# esp_all.net
KiCad netlist of a schematic drawn in EAGLE
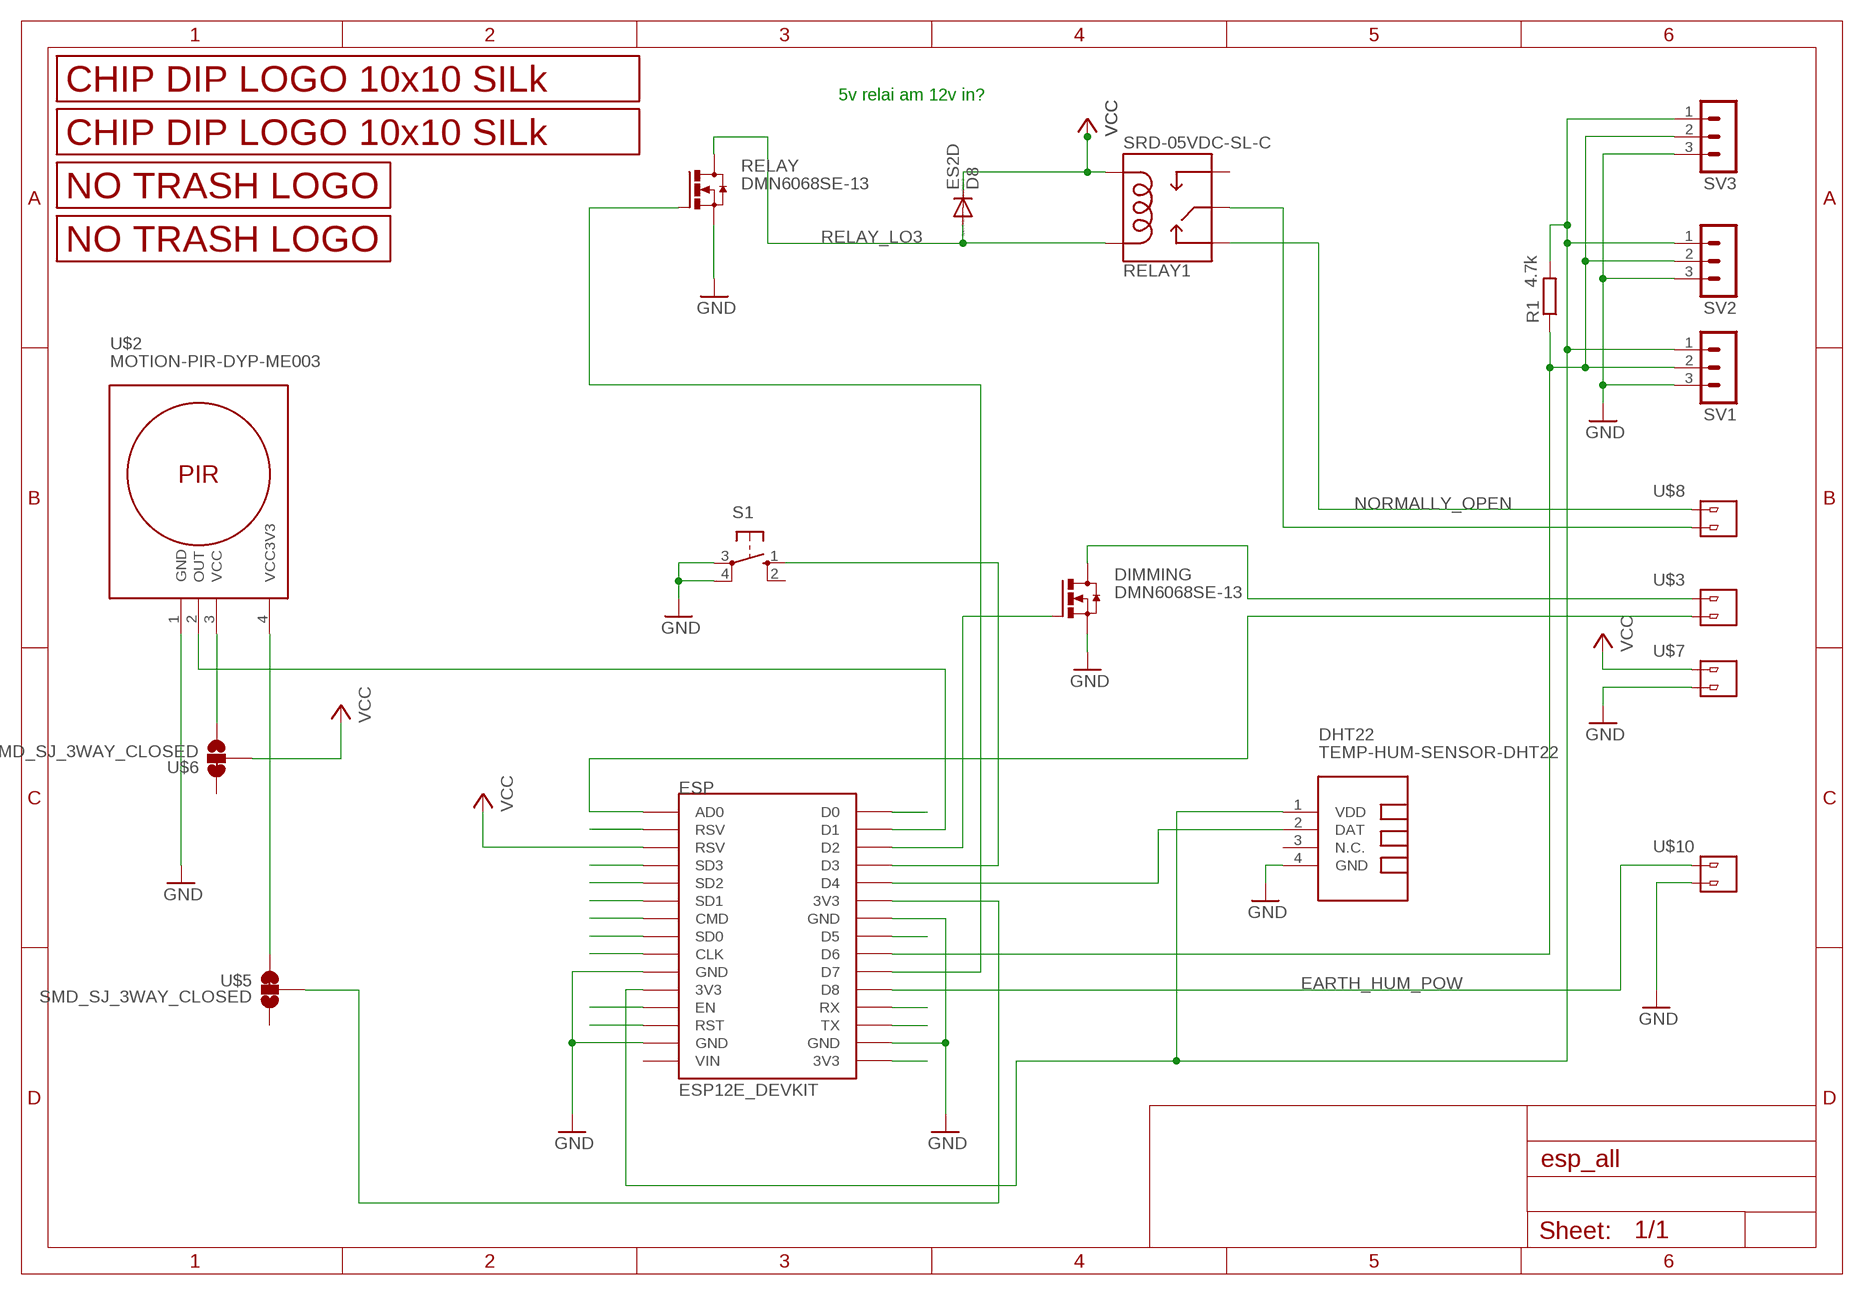
[diagram p0: schematic, sheet 1]

(export (version "E")
  (design (tool "Eeschema 10.0.6"))
  (components
    (comp (ref "D8")
      (value "ES2D")
      (footprint "eagle-import:SMB")
      (libsource (lib "eagle-import") (part "DIODE-SMB"))
    )
    (comp (ref "DHT22")
      (value "TEMP-HUM-SENSOR-DHT22")
      (footprint "eagle-import:TEMP-HUM-SENSOR-DHT22")
      (libsource (lib "eagle-import") (part "TEMP-HUM-SENSOR-DHT22"))
    )
    (comp (ref "DIMMING")
      (value "DMN6068SE-13")
      (footprint "eagle-import:SOT223")
      (libsource (lib "eagle-import") (part "NMOSFET_SMD_223"))
    )
    (comp (ref "ESP")
      (value "ESP12E_DEVKIT")
      (footprint "eagle-import:ESP12E_DEVKIT")
      (libsource (lib "eagle-import") (part "ESP12E_DEVKIT"))
    )
    (comp (ref "R1")
      (value "4.7k")
      (footprint "eagle-import:M0805")
      (libsource (lib "eagle-import") (part "R-EU_M0805"))
    )
    (comp (ref "RELAY")
      (value "DMN6068SE-13")
      (footprint "eagle-import:SOT223")
      (libsource (lib "eagle-import") (part "NMOSFET_SMD_223"))
    )
    (comp (ref "RELAY1")
      (value "SRD-05VDC-SL-C")
      (footprint "eagle-import:SRD-05VDC-SL-C")
      (libsource (lib "eagle-import") (part "RELAYPTH"))
    )
    (comp (ref "S1")
      (value "40/XX")
      (footprint "eagle-import:B3F_40XX")
      (libsource (lib "eagle-import") (part "40/XX"))
    )
    (comp (ref "SV1")
      (value "MA03-1")
      (footprint "eagle-import:MA03-1")
      (libsource (lib "eagle-import") (part "MA03-1"))
    )
    (comp (ref "SV2")
      (value "MA03-1")
      (footprint "eagle-import:MA03-1")
      (libsource (lib "eagle-import") (part "MA03-1"))
    )
    (comp (ref "SV3")
      (value "MA03-1")
      (footprint "eagle-import:MA03-1")
      (libsource (lib "eagle-import") (part "MA03-1"))
    )
    (comp (ref "U$1")
      (value "LOGO_10X10_SILK")
      (footprint "eagle-import:LOGO2_10X10_SILK")
      (libsource (lib "eagle-import") (part "LOGO_10X10_SILK"))
    )
    (comp (ref "U$2")
      (value "MOTION-PIR-DYP-ME003")
      (footprint "eagle-import:MOTION-PIR-DYP-ME003")
      (libsource (lib "eagle-import") (part "MOTION-PIR-DYP-ME003"))
    )
    (comp (ref "U$3")
      (value "V1")
      (footprint "eagle-import:2_SCREW_PIN")
      (libsource (lib "eagle-import") (part "2_PIN_CONNECTOR"))
    )
    (comp (ref "U$4")
      (value "LOGO_NO_TRASHNO_TRASH")
      (footprint "eagle-import:LOGO_ROHS_NO_TRASH")
      (libsource (lib "eagle-import") (part "LOGO_NO_TRASHNO_TRASH"))
    )
    (comp (ref "U$5")
      (value "SMD_SJ_3WAY_CLOSED")
      (footprint "eagle-import:SMD_SJ_3WAY_CLOSED")
      (libsource (lib "eagle-import") (part "SMD_SJ_3WAY_CLOSED"))
    )
    (comp (ref "U$6")
      (value "SMD_SJ_3WAY_CLOSED")
      (footprint "eagle-import:SMD_SJ_3WAY_CLOSED")
      (libsource (lib "eagle-import") (part "SMD_SJ_3WAY_CLOSED"))
    )
    (comp (ref "U$7")
      (value "V1")
      (footprint "eagle-import:2_SCREW_PIN")
      (libsource (lib "eagle-import") (part "2_PIN_CONNECTOR"))
    )
    (comp (ref "U$8")
      (value "V1")
      (footprint "eagle-import:2_SCREW_PIN")
      (libsource (lib "eagle-import") (part "2_PIN_CONNECTOR"))
    )
    (comp (ref "U$9")
      (value "LOGO_NO_TRASHROHS")
      (footprint "eagle-import:LOGO_ROHS_SYM")
      (libsource (lib "eagle-import") (part "LOGO_NO_TRASHROHS"))
    )
    (comp (ref "U$10")
      (value "V1")
      (footprint "eagle-import:2_SCREW_PIN")
      (libsource (lib "eagle-import") (part "2_PIN_CONNECTOR"))
    )
    (comp (ref "U$11")
      (value "LOGO_10X10_SILK")
      (footprint "eagle-import:LOGO2_10X10_SILK")
      (libsource (lib "eagle-import") (part "LOGO_10X10_SILK"))
    )
  )
  (nets
    (net (code "1") (name "/EARTH_HUM_POW") (class "Default")
      (node (ref "ESP") (pin "D8") (pinfunction "D8_D8") (pintype "bidirectional"))
      (node (ref "U$10") (pin "P$1") (pinfunction "1_P$1") (pintype "passive"))
    )
    (net (code "2") (name "/NORMALLY_OPEN") (class "Default")
      (node (ref "RELAY1") (pin "SWCLOSED") (pinfunction "SWCLOSE_SWCLOSED") (pintype "bidirectional"))
      (node (ref "U$8") (pin "P$1") (pinfunction "1_P$1") (pintype "passive"))
    )
    (net (code "3") (name "/RELAY_LO3") (class "Default")
      (node (ref "D8") (pin "A") (pinfunction "A_A") (pintype "passive"))
      (node (ref "RELAY") (pin "2") (pinfunction "D_2") (pintype "passive"))
      (node (ref "RELAY") (pin "4") (pinfunction "D_4") (pintype "passive"))
      (node (ref "RELAY1") (pin "COIL1") (pinfunction "COIL1_COIL1") (pintype "bidirectional"))
    )
    (net (code "4") (name "GND") (class "Default")
      (node (ref "DHT22") (pin "4") (pinfunction "GND_4") (pintype "power_in"))
      (node (ref "DIMMING") (pin "3") (pinfunction "S_3") (pintype "passive"))
      (node (ref "ESP") (pin "GND@0") (pinfunction "GND_GND@0") (pintype "bidirectional"))
      (node (ref "ESP") (pin "GND@1") (pinfunction "GND_GND@1") (pintype "bidirectional"))
      (node (ref "ESP") (pin "GND@2") (pinfunction "GND_GND@2") (pintype "bidirectional"))
      (node (ref "ESP") (pin "GND@3") (pinfunction "GND_GND@3") (pintype "bidirectional"))
      (node (ref "RELAY") (pin "3") (pinfunction "S_3") (pintype "passive"))
      (node (ref "S1") (pin "3") (pinfunction "P_3") (pintype "passive"))
      (node (ref "S1") (pin "4") (pinfunction "P1_4") (pintype "passive"))
      (node (ref "SV1") (pin "3") (pinfunction "3_3") (pintype "passive"))
      (node (ref "SV2") (pin "3") (pinfunction "3_3") (pintype "passive"))
      (node (ref "SV3") (pin "3") (pinfunction "3_3") (pintype "passive"))
      (node (ref "U$10") (pin "P$2") (pinfunction "2_P$2") (pintype "passive"))
      (node (ref "U$2") (pin "1") (pinfunction "GND_1") (pintype "power_in"))
      (node (ref "U$7") (pin "P$2") (pinfunction "2_P$2") (pintype "passive"))
    )
    (net (code "5") (name "Net-(DHT22-DAT)") (class "Default")
      (node (ref "DHT22") (pin "2") (pinfunction "DAT_2") (pintype "bidirectional"))
      (node (ref "ESP") (pin "D4") (pinfunction "D4_D4") (pintype "bidirectional"))
    )
    (net (code "6") (name "Net-(DHT22-VDD)") (class "Default")
      (node (ref "DHT22") (pin "1") (pinfunction "VDD_1") (pintype "power_in"))
      (node (ref "ESP") (pin "3V3@0") (pinfunction "3V3_3V3@0") (pintype "bidirectional"))
      (node (ref "R1") (pin "2") (pinfunction "2_2") (pintype "passive"))
      (node (ref "SV1") (pin "1") (pinfunction "1_1") (pintype "passive"))
      (node (ref "SV2") (pin "1") (pinfunction "1_1") (pintype "passive"))
      (node (ref "SV3") (pin "1") (pinfunction "1_1") (pintype "passive"))
    )
    (net (code "7") (name "Net-(DIMMING-G)") (class "Default")
      (node (ref "DIMMING") (pin "1") (pinfunction "G_1") (pintype "passive"))
      (node (ref "ESP") (pin "D2") (pinfunction "D2_D2") (pintype "bidirectional"))
    )
    (net (code "8") (name "Net-(ESP-3V3-Pad3V3@1)") (class "Default")
      (node (ref "ESP") (pin "3V3@1") (pinfunction "3V3_3V3@1") (pintype "bidirectional"))
      (node (ref "U$5") (pin "2") (pinfunction "2_2") (pintype "passive"))
    )
    (net (code "9") (name "Net-(ESP-PadD6)") (class "Default")
      (node (ref "ESP") (pin "D6") (pinfunction "D6_D6") (pintype "bidirectional"))
      (node (ref "R1") (pin "1") (pinfunction "1_1") (pintype "passive"))
      (node (ref "SV1") (pin "2") (pinfunction "2_2") (pintype "passive"))
      (node (ref "SV2") (pin "2") (pinfunction "2_2") (pintype "passive"))
      (node (ref "SV3") (pin "2") (pinfunction "2_2") (pintype "passive"))
    )
    (net (code "10") (name "Net-(RELAY-G)") (class "Default")
      (node (ref "ESP") (pin "D7") (pinfunction "D7_D7") (pintype "bidirectional"))
      (node (ref "RELAY") (pin "1") (pinfunction "G_1") (pintype "passive"))
    )
    (net (code "11") (name "Net-(S1-S)") (class "Default")
      (node (ref "ESP") (pin "D3") (pinfunction "D3_D3") (pintype "bidirectional"))
      (node (ref "S1") (pin "1") (pinfunction "S_1") (pintype "passive"))
    )
    (net (code "12") (name "Net-(U$2-OUT)") (class "Default")
      (node (ref "ESP") (pin "D1") (pinfunction "D1_D1") (pintype "bidirectional"))
      (node (ref "U$2") (pin "2") (pinfunction "OUT_2") (pintype "output"))
    )
    (net (code "13") (name "Net-(U$2-VCC)") (class "Default")
      (node (ref "U$2") (pin "3") (pinfunction "VCC_3") (pintype "power_in"))
      (node (ref "U$6") (pin "3") (pinfunction "3_3") (pintype "passive"))
    )
    (net (code "14") (name "Net-(U$2-VCC3V3)") (class "Default")
      (node (ref "U$2") (pin "4") (pinfunction "VCC3V3_4") (pintype "power_in"))
      (node (ref "U$5") (pin "1") (pinfunction "1_1") (pintype "passive"))
    )
    (net (code "15") (name "Net-(U$3-1)") (class "Default")
      (node (ref "DIMMING") (pin "2") (pinfunction "D_2") (pintype "passive"))
      (node (ref "DIMMING") (pin "4") (pinfunction "D_4") (pintype "passive"))
      (node (ref "U$3") (pin "P$1") (pinfunction "1_P$1") (pintype "passive"))
    )
    (net (code "16") (name "Net-(U$3-2)") (class "Default")
      (node (ref "ESP") (pin "AD0") (pinfunction "AD0_AD0") (pintype "bidirectional"))
      (node (ref "U$3") (pin "P$2") (pinfunction "2_P$2") (pintype "passive"))
    )
    (net (code "17") (name "Net-(U$8-2)") (class "Default")
      (node (ref "RELAY1") (pin "SWCOMMON") (pinfunction "SWCOMMON_SWCOMMON") (pintype "bidirectional"))
      (node (ref "U$8") (pin "P$2") (pinfunction "2_P$2") (pintype "passive"))
    )
    (net (code "18") (name "VCC") (class "Default")
      (node (ref "D8") (pin "C") (pinfunction "C_C") (pintype "passive"))
      (node (ref "ESP") (pin "RSV@1") (pinfunction "RSV_RSV@1") (pintype "bidirectional"))
      (node (ref "RELAY1") (pin "COIL0") (pinfunction "COIL0_COIL0") (pintype "bidirectional"))
      (node (ref "U$6") (pin "2") (pinfunction "2_2") (pintype "passive"))
      (node (ref "U$7") (pin "P$1") (pinfunction "1_P$1") (pintype "passive"))
    )
    (net (code "19") (name "unconnected-(DHT22-N.C.-Pad3)") (class "Default")
      (node (ref "DHT22") (pin "3") (pinfunction "N.C._3") (pintype "passive"))
    )
    (net (code "20") (name "unconnected-(ESP-3V3-Pad3V3@2)") (class "Default")
      (node (ref "ESP") (pin "3V3@2") (pinfunction "3V3_3V3@2") (pintype "bidirectional"))
    )
    (net (code "21") (name "unconnected-(ESP-PadCLK)") (class "Default")
      (node (ref "ESP") (pin "CLK") (pinfunction "CLK_CLK") (pintype "bidirectional"))
    )
    (net (code "22") (name "unconnected-(ESP-PadCMD)") (class "Default")
      (node (ref "ESP") (pin "CMD") (pinfunction "CMD_CMD") (pintype "bidirectional"))
    )
    (net (code "23") (name "unconnected-(ESP-PadD0)") (class "Default")
      (node (ref "ESP") (pin "D0") (pinfunction "D0_D0") (pintype "bidirectional"))
    )
    (net (code "24") (name "unconnected-(ESP-PadD5)") (class "Default")
      (node (ref "ESP") (pin "D5") (pinfunction "D5_D5") (pintype "bidirectional"))
    )
    (net (code "25") (name "unconnected-(ESP-PadEN)") (class "Default")
      (node (ref "ESP") (pin "EN") (pinfunction "EN_EN") (pintype "bidirectional"))
    )
    (net (code "26") (name "unconnected-(ESP-PadRST)") (class "Default")
      (node (ref "ESP") (pin "RST") (pinfunction "RST_RST") (pintype "bidirectional"))
    )
    (net (code "27") (name "unconnected-(ESP-PadRX)") (class "Default")
      (node (ref "ESP") (pin "RX") (pinfunction "RX_RX") (pintype "bidirectional"))
    )
    (net (code "28") (name "unconnected-(ESP-PadSD0)") (class "Default")
      (node (ref "ESP") (pin "SD0") (pinfunction "SD0_SD0") (pintype "bidirectional"))
    )
    (net (code "29") (name "unconnected-(ESP-PadSD1)") (class "Default")
      (node (ref "ESP") (pin "SD1") (pinfunction "SD1_SD1") (pintype "bidirectional"))
    )
    (net (code "30") (name "unconnected-(ESP-PadSD2)") (class "Default")
      (node (ref "ESP") (pin "SD2") (pinfunction "SD2_SD2") (pintype "bidirectional"))
    )
    (net (code "31") (name "unconnected-(ESP-PadSD3)") (class "Default")
      (node (ref "ESP") (pin "SD3") (pinfunction "SD3_SD3") (pintype "bidirectional"))
    )
    (net (code "32") (name "unconnected-(ESP-PadTX)") (class "Default")
      (node (ref "ESP") (pin "TX") (pinfunction "TX_TX") (pintype "bidirectional"))
    )
    (net (code "33") (name "unconnected-(ESP-PadVIN)") (class "Default")
      (node (ref "ESP") (pin "VIN") (pinfunction "VIN_VIN") (pintype "bidirectional"))
    )
    (net (code "34") (name "unconnected-(ESP-RSV-PadRSV@0)") (class "Default")
      (node (ref "ESP") (pin "RSV@0") (pinfunction "RSV_RSV@0") (pintype "bidirectional"))
    )
    (net (code "35") (name "unconnected-(RELAY1-PadSWOPEN)") (class "Default")
      (node (ref "RELAY1") (pin "SWOPEN") (pinfunction "SWOPEN_SWOPEN") (pintype "bidirectional"))
    )
    (net (code "36") (name "unconnected-(S1-S1-Pad2)") (class "Default")
      (node (ref "S1") (pin "2") (pinfunction "S1_2") (pintype "passive"))
    )
    (net (code "37") (name "unconnected-(U$5-Pad3)") (class "Default")
      (node (ref "U$5") (pin "3") (pinfunction "3_3") (pintype "passive"))
    )
    (net (code "38") (name "unconnected-(U$6-Pad1)") (class "Default")
      (node (ref "U$6") (pin "1") (pinfunction "1_1") (pintype "passive"))
    )
  )
)
